# 5v_4v.net
KiCad netlist of a schematic drawn in Altium Designer
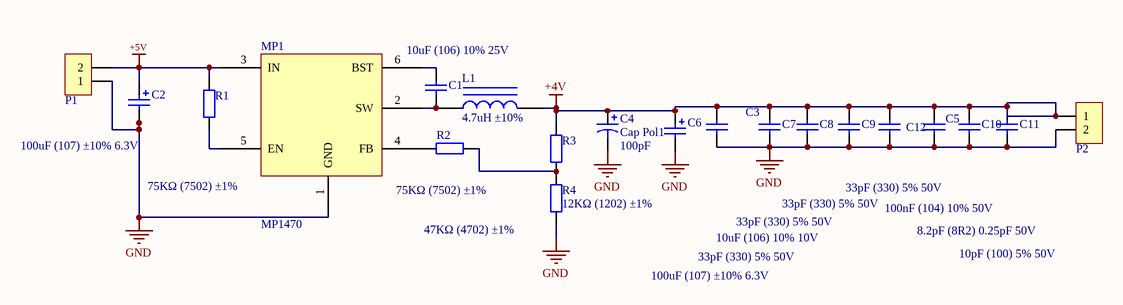
[diagram p0: 5v_4v.SchDoc]

(export (version "E")
  (design (tool "Eeschema 10.0.6"))
  (components
    (comp (ref "C1")
      (value "10uF (106) 10% 25V")
      (footprint "0805_C")
      (description "贴片电容")
      (libsource (lib "Miscellaneous Devices LC") (part "0805 10uF (106) 10% 25V"))
    )
    (comp (ref "C2")
      (value "100uF (107) ±10% 6.3V")
      (footprint "CASE-B_3528")
      (description "钽电容")
      (libsource (lib "Miscellaneous Devices LC") (part "3528 100uF (107) 10% 6.3V"))
    )
    (comp (ref "C3")
      (value "10uF (106) 10% 10V")
      (footprint "0603_C")
      (description "贴片电容")
      (libsource (lib "Miscellaneous Devices LC") (part "0603 10uF (106) 10% 10V"))
    )
    (comp (ref "C4")
      (value "Cap Pol1")
      (footprint "C7361")
      (description "Polarized Capacitor (Radial)")
      (fields (field (name "ALTIUM_VALUE") "100pF") (field (name "PUBLISHER") "Altium Limited"))
      (libsource (lib "Miscellaneous Devices") (part "Cap Pol1"))
    )
    (comp (ref "C5")
      (value "100nF (104) 10% 50V")
      (footprint "0603_C")
      (description "贴片电容")
      (libsource (lib "Miscellaneous Devices LC") (part "0603 100nF (104) 10% 50V"))
    )
    (comp (ref "C6")
      (value "100uF (107) ±10% 6.3V")
      (footprint "CASE-B_3528")
      (description "钽电容")
      (libsource (lib "Miscellaneous Devices LC") (part "3528 100uF (107) 10% 6.3V"))
    )
    (comp (ref "C7")
      (value "33pF (330) 5% 50V")
      (footprint "0603_C")
      (description "贴片电容")
      (libsource (lib "Miscellaneous Devices LC") (part "0603 33pF (330) 5% 50V"))
    )
    (comp (ref "C8")
      (value "33pF (330) 5% 50V")
      (footprint "0603_C")
      (description "贴片电容")
      (libsource (lib "Miscellaneous Devices LC") (part "0603 33pF (330) 5% 50V"))
    )
    (comp (ref "C9")
      (value "33pF (330) 5% 50V")
      (footprint "0603_C")
      (description "贴片电容")
      (libsource (lib "Miscellaneous Devices LC") (part "0603 33pF (330) 5% 50V"))
    )
    (comp (ref "C10")
      (value "8.2pF (8R2) 0.25pF 50V")
      (footprint "0603_C")
      (description "贴片电容")
      (libsource (lib "Miscellaneous Devices LC") (part "0603 8.2pF (8R2) 0.25pF 50V"))
    )
    (comp (ref "C11")
      (value "10pF (100) 5% 50V")
      (footprint "0603_C")
      (description "贴片电容")
      (libsource (lib "Miscellaneous Devices LC") (part "0603 10pF (100) 5% 50V"))
    )
    (comp (ref "C12")
      (value "33pF (330) 5% 50V")
      (footprint "0603_C")
      (description "贴片电容")
      (libsource (lib "Miscellaneous Devices LC") (part "0603 33pF (330) 5% 50V"))
    )
    (comp (ref "L1")
      (value "4.7uH ±10%")
      (footprint "C8X10")
      (description "贴片电感")
      (libsource (lib "Miscellaneous Devices LC") (part "0603 4.7uH 10%"))
    )
    (comp (ref "MP1") (value "MP1470") (footprint "SOT-23-6M") (libsource (lib "Schlib1") (part "MP1470")))
    (comp (ref "P1")
      (value "HDR-1X2")
      (footprint "XH2.54-2")
      (description "2P接插件")
      (fields (field (name "版权归属") "源创客"))
      (libsource (lib "") (part "Header 2_1"))
    )
    (comp (ref "P2")
      (value "HDR-1X2")
      (footprint "XH2.54-2")
      (description "2P接插件")
      (fields (field (name "版权归属") "源创客"))
      (libsource (lib "接插件") (part "Header 2"))
    )
    (comp (ref "R1")
      (value "75KΩ (7502) ±1%")
      (footprint "0603_R")
      (description "贴片电阻")
      (libsource (lib "") (part "0603 75KΩ (7502) 1%_1"))
    )
    (comp (ref "R2")
      (value "75KΩ (7502) ±1%")
      (footprint "0603_R")
      (description "贴片电阻")
      (libsource (lib "Miscellaneous Devices LC") (part "0603 75KΩ (7502) 1%"))
    )
    (comp (ref "R3")
      (value "47KΩ (4702) ±1%")
      (footprint "0603_R")
      (description "贴片电阻")
      (libsource (lib "Miscellaneous Devices LC") (part "0603 47KΩ (4702) 1%"))
    )
    (comp (ref "R4")
      (value "12KΩ (1202) ±1%")
      (footprint "0603_R")
      (description "贴片电阻")
      (libsource (lib "Miscellaneous Devices LC") (part "0603 12KΩ (1202) 1%"))
    )
  )
  (nets
    (net (code "1") (name "+4V") (class "Default")
      (node (ref "C10") (pin "2") (pinfunction "2_2") (pintype "passive"))
      (node (ref "C11") (pin "2") (pinfunction "2_2") (pintype "passive"))
      (node (ref "C12") (pin "2") (pinfunction "2_2") (pintype "passive"))
      (node (ref "C3") (pin "1") (pinfunction "1_1") (pintype "passive"))
      (node (ref "C4") (pin "1") (pinfunction "1_1") (pintype "passive"))
      (node (ref "C5") (pin "2") (pinfunction "2_2") (pintype "passive"))
      (node (ref "C6") (pin "1") (pinfunction "1_1") (pintype "passive"))
      (node (ref "C7") (pin "2") (pinfunction "2_2") (pintype "passive"))
      (node (ref "C8") (pin "2") (pinfunction "2_2") (pintype "passive"))
      (node (ref "C9") (pin "2") (pinfunction "2_2") (pintype "passive"))
      (node (ref "L1") (pin "2") (pinfunction "2_2") (pintype "passive"))
      (node (ref "P2") (pin "1") (pinfunction "1_1") (pintype "passive"))
      (node (ref "R3") (pin "2") (pinfunction "2_2") (pintype "passive"))
    )
    (net (code "2") (name "+5V") (class "Default")
      (node (ref "C2") (pin "1") (pinfunction "1_1") (pintype "passive"))
      (node (ref "MP1") (pin "3") (pinfunction "IN_3") (pintype "passive"))
      (node (ref "P1") (pin "2") (pinfunction "2_2") (pintype "passive"))
      (node (ref "R1") (pin "2") (pinfunction "2_2") (pintype "passive"))
    )
    (net (code "3") (name "GND") (class "Default")
      (node (ref "C10") (pin "1") (pinfunction "1_1") (pintype "passive"))
      (node (ref "C11") (pin "1") (pinfunction "1_1") (pintype "passive"))
      (node (ref "C12") (pin "1") (pinfunction "1_1") (pintype "passive"))
      (node (ref "C2") (pin "2") (pinfunction "2_2") (pintype "passive"))
      (node (ref "C3") (pin "2") (pinfunction "2_2") (pintype "passive"))
      (node (ref "C4") (pin "2") (pinfunction "2_2") (pintype "passive"))
      (node (ref "C5") (pin "1") (pinfunction "1_1") (pintype "passive"))
      (node (ref "C6") (pin "2") (pinfunction "2_2") (pintype "passive"))
      (node (ref "C7") (pin "1") (pinfunction "1_1") (pintype "passive"))
      (node (ref "C8") (pin "1") (pinfunction "1_1") (pintype "passive"))
      (node (ref "C9") (pin "1") (pinfunction "1_1") (pintype "passive"))
      (node (ref "MP1") (pin "1") (pinfunction "GND_1") (pintype "passive"))
      (node (ref "P1") (pin "1") (pinfunction "1_1") (pintype "passive"))
      (node (ref "P2") (pin "2") (pinfunction "2_2") (pintype "passive"))
      (node (ref "R4") (pin "1") (pinfunction "1_1") (pintype "passive"))
    )
    (net (code "4") (name "Net-(MP1-BST)") (class "Default")
      (node (ref "C1") (pin "2") (pinfunction "2_2") (pintype "passive"))
      (node (ref "MP1") (pin "6") (pinfunction "BST_6") (pintype "passive"))
    )
    (net (code "5") (name "Net-(MP1-EN)") (class "Default")
      (node (ref "MP1") (pin "5") (pinfunction "EN_5") (pintype "passive"))
      (node (ref "R1") (pin "1") (pinfunction "1_1") (pintype "passive"))
    )
    (net (code "6") (name "Net-(MP1-FB)") (class "Default")
      (node (ref "MP1") (pin "4") (pinfunction "FB_4") (pintype "passive"))
      (node (ref "R2") (pin "1") (pinfunction "1_1") (pintype "passive"))
    )
    (net (code "7") (name "Net-(MP1-SW)") (class "Default")
      (node (ref "C1") (pin "1") (pinfunction "1_1") (pintype "passive"))
      (node (ref "L1") (pin "1") (pinfunction "1_1") (pintype "passive"))
      (node (ref "MP1") (pin "2") (pinfunction "SW_2") (pintype "passive"))
    )
    (net (code "8") (name "Net-(R2-Pad2)") (class "Default")
      (node (ref "R2") (pin "2") (pinfunction "2_2") (pintype "passive"))
      (node (ref "R3") (pin "1") (pinfunction "1_1") (pintype "passive"))
      (node (ref "R4") (pin "2") (pinfunction "2_2") (pintype "passive"))
    )
  )
)
